# LEDs.net
KiCad netlist of a schematic drawn in Altium Designer
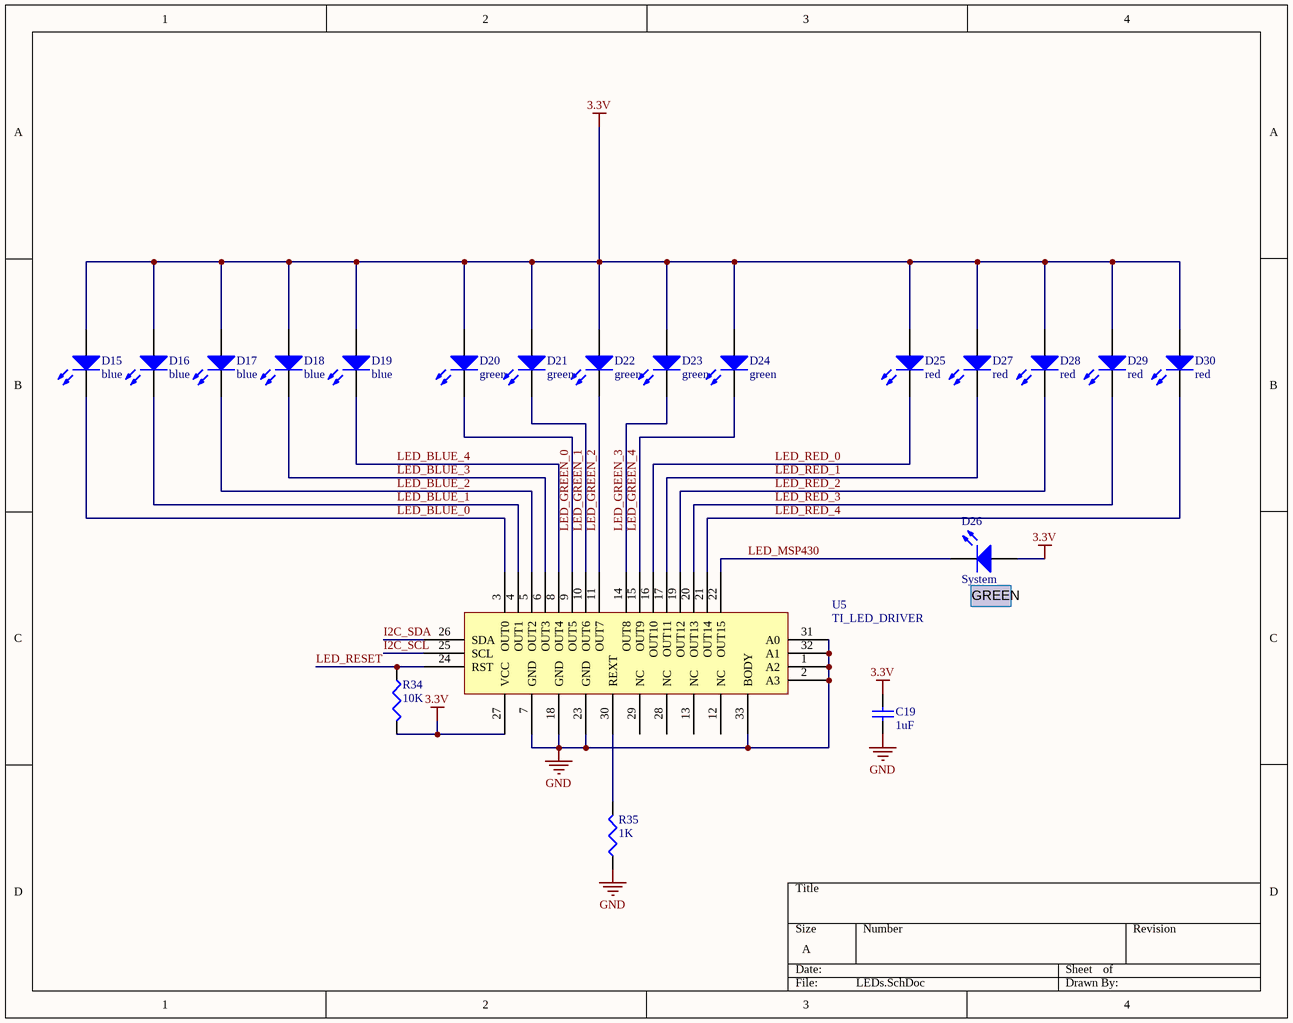
[diagram p0: LEDs.SchDoc]

(export (version "E")
  (design (tool "Eeschema 10.0.6"))
  (components
    (comp (ref "C19")
      (value "1uF")
      (footprint "CAPC1608L")
      (description "Capacitor (Semiconductor SIM Model)")
      (fields (field (name "Comment") "Cap Semi") (field (name "PUBLISHER") "Altium Limited"))
      (libsource (lib "Miscellaneous Devices") (part "Cap Semi"))
    )
    (comp (ref "D15") (value "blue") (footprint "SurfaceMount(603)") (libsource (lib "mrone") (part "LED")))
    (comp (ref "D16") (value "blue") (footprint "SurfaceMount(603)") (libsource (lib "mrone") (part "LED")))
    (comp (ref "D17") (value "blue") (footprint "SurfaceMount(603)") (libsource (lib "mrone") (part "LED")))
    (comp (ref "D18") (value "blue") (footprint "SurfaceMount(603)") (libsource (lib "mrone") (part "LED")))
    (comp (ref "D19") (value "blue") (footprint "SurfaceMount(603)") (libsource (lib "mrone") (part "LED")))
    (comp (ref "D20") (value "green") (footprint "SurfaceMount(603)") (libsource (lib "mrone") (part "LED")))
    (comp (ref "D21") (value "green") (footprint "SurfaceMount(603)") (libsource (lib "mrone") (part "LED")))
    (comp (ref "D22") (value "green") (footprint "SurfaceMount(603)") (libsource (lib "mrone") (part "LED")))
    (comp (ref "D23") (value "green") (footprint "SurfaceMount(603)") (libsource (lib "mrone") (part "LED")))
    (comp (ref "D24") (value "green") (footprint "SurfaceMount(603)") (libsource (lib "mrone") (part "LED")))
    (comp (ref "D25") (value "red") (footprint "SurfaceMount(603)") (libsource (lib "mrone") (part "LED")))
    (comp (ref "D26") (value "System") (footprint "SurfaceMount(603)") (libsource (lib "") (part "LED_1")))
    (comp (ref "D27") (value "red") (footprint "SurfaceMount(603)") (libsource (lib "mrone") (part "LED")))
    (comp (ref "D28") (value "red") (footprint "SurfaceMount(603)") (libsource (lib "mrone") (part "LED")))
    (comp (ref "D29") (value "red") (footprint "SurfaceMount(603)") (libsource (lib "mrone") (part "LED")))
    (comp (ref "D30") (value "red") (footprint "SurfaceMount(603)") (libsource (lib "mrone") (part "LED")))
    (comp (ref "R34")
      (value "10K")
      (footprint "RESC1608L")
      (description "Resistor")
      (fields (field (name "Comment") "Res3") (field (name "PUBLISHER") "Altium Limited"))
      (libsource (lib "Miscellaneous Devices") (part "Res3"))
    )
    (comp (ref "R35")
      (value "1K")
      (footprint "RESC1608L")
      (description "Resistor")
      (fields (field (name "Comment") "Res3") (field (name "PUBLISHER") "Altium Limited"))
      (libsource (lib "Miscellaneous Devices") (part "Res3"))
    )
    (comp (ref "U5")
      (value "TI_LED_DRIVER")
      (footprint "QFN32-LEDTLC59116")
      (libsource (lib "mrone") (part "TLC59116LEDDRIVER"))
    )
  )
  (nets
    (net (code "1") (name "/I2C_SCL") (class "Default")
      (node (ref "U5") (pin "25") (pinfunction "SCL_25") (pintype "passive"))
    )
    (net (code "2") (name "/I2C_SDA") (class "Default")
      (node (ref "U5") (pin "26") (pinfunction "SDA_26") (pintype "passive"))
    )
    (net (code "3") (name "/LED_BLUE_0") (class "Default")
      (node (ref "D15") (pin "2") (pinfunction "K_2") (pintype "passive"))
      (node (ref "U5") (pin "3") (pinfunction "OUT0_3") (pintype "passive"))
    )
    (net (code "4") (name "/LED_BLUE_1") (class "Default")
      (node (ref "D16") (pin "2") (pinfunction "K_2") (pintype "passive"))
      (node (ref "U5") (pin "4") (pinfunction "OUT1_4") (pintype "passive"))
    )
    (net (code "5") (name "/LED_BLUE_2") (class "Default")
      (node (ref "D17") (pin "2") (pinfunction "K_2") (pintype "passive"))
      (node (ref "U5") (pin "5") (pinfunction "OUT2_5") (pintype "passive"))
    )
    (net (code "6") (name "/LED_BLUE_3") (class "Default")
      (node (ref "D18") (pin "2") (pinfunction "K_2") (pintype "passive"))
      (node (ref "U5") (pin "6") (pinfunction "OUT3_6") (pintype "passive"))
    )
    (net (code "7") (name "/LED_BLUE_4") (class "Default")
      (node (ref "D19") (pin "2") (pinfunction "K_2") (pintype "passive"))
      (node (ref "U5") (pin "8") (pinfunction "OUT4_8") (pintype "passive"))
    )
    (net (code "8") (name "/LED_GREEN_0") (class "Default")
      (node (ref "D20") (pin "2") (pinfunction "K_2") (pintype "passive"))
      (node (ref "U5") (pin "9") (pinfunction "OUT5_9") (pintype "passive"))
    )
    (net (code "9") (name "/LED_GREEN_1") (class "Default")
      (node (ref "D21") (pin "2") (pinfunction "K_2") (pintype "passive"))
      (node (ref "U5") (pin "10") (pinfunction "OUT6_10") (pintype "passive"))
    )
    (net (code "10") (name "/LED_GREEN_2") (class "Default")
      (node (ref "D22") (pin "2") (pinfunction "K_2") (pintype "passive"))
      (node (ref "U5") (pin "11") (pinfunction "OUT7_11") (pintype "passive"))
    )
    (net (code "11") (name "/LED_GREEN_3") (class "Default")
      (node (ref "D23") (pin "2") (pinfunction "K_2") (pintype "passive"))
      (node (ref "U5") (pin "14") (pinfunction "OUT8_14") (pintype "passive"))
    )
    (net (code "12") (name "/LED_GREEN_4") (class "Default")
      (node (ref "D24") (pin "2") (pinfunction "K_2") (pintype "passive"))
      (node (ref "U5") (pin "15") (pinfunction "OUT9_15") (pintype "passive"))
    )
    (net (code "13") (name "/LED_MSP430") (class "Default")
      (node (ref "D26") (pin "2") (pinfunction "K_2") (pintype "passive"))
      (node (ref "U5") (pin "22") (pinfunction "OUT15_22") (pintype "passive"))
    )
    (net (code "14") (name "/LED_RED_0") (class "Default")
      (node (ref "D25") (pin "2") (pinfunction "K_2") (pintype "passive"))
      (node (ref "U5") (pin "16") (pinfunction "OUT10_16") (pintype "passive"))
    )
    (net (code "15") (name "/LED_RED_1") (class "Default")
      (node (ref "D27") (pin "2") (pinfunction "K_2") (pintype "passive"))
      (node (ref "U5") (pin "17") (pinfunction "OUT11_17") (pintype "passive"))
    )
    (net (code "16") (name "/LED_RED_2") (class "Default")
      (node (ref "D28") (pin "2") (pinfunction "K_2") (pintype "passive"))
      (node (ref "U5") (pin "19") (pinfunction "OUT12_19") (pintype "passive"))
    )
    (net (code "17") (name "/LED_RED_3") (class "Default")
      (node (ref "D29") (pin "2") (pinfunction "K_2") (pintype "passive"))
      (node (ref "U5") (pin "20") (pinfunction "OUT13_20") (pintype "passive"))
    )
    (net (code "18") (name "/LED_RED_4") (class "Default")
      (node (ref "D30") (pin "2") (pinfunction "K_2") (pintype "passive"))
      (node (ref "U5") (pin "21") (pinfunction "OUT14_21") (pintype "passive"))
    )
    (net (code "19") (name "/LED_RESET") (class "Default")
      (node (ref "R34") (pin "1") (pinfunction "1_1") (pintype "passive"))
      (node (ref "U5") (pin "24") (pinfunction "RST_24") (pintype "passive"))
    )
    (net (code "20") (name "3.3V") (class "Default")
      (node (ref "C19") (pin "2") (pinfunction "2_2") (pintype "passive"))
      (node (ref "D15") (pin "1") (pinfunction "A_1") (pintype "passive"))
      (node (ref "D16") (pin "1") (pinfunction "A_1") (pintype "passive"))
      (node (ref "D17") (pin "1") (pinfunction "A_1") (pintype "passive"))
      (node (ref "D18") (pin "1") (pinfunction "A_1") (pintype "passive"))
      (node (ref "D19") (pin "1") (pinfunction "A_1") (pintype "passive"))
      (node (ref "D20") (pin "1") (pinfunction "A_1") (pintype "passive"))
      (node (ref "D21") (pin "1") (pinfunction "A_1") (pintype "passive"))
      (node (ref "D22") (pin "1") (pinfunction "A_1") (pintype "passive"))
      (node (ref "D23") (pin "1") (pinfunction "A_1") (pintype "passive"))
      (node (ref "D24") (pin "1") (pinfunction "A_1") (pintype "passive"))
      (node (ref "D25") (pin "1") (pinfunction "A_1") (pintype "passive"))
      (node (ref "D26") (pin "1") (pinfunction "A_1") (pintype "passive"))
      (node (ref "D27") (pin "1") (pinfunction "A_1") (pintype "passive"))
      (node (ref "D28") (pin "1") (pinfunction "A_1") (pintype "passive"))
      (node (ref "D29") (pin "1") (pinfunction "A_1") (pintype "passive"))
      (node (ref "D30") (pin "1") (pinfunction "A_1") (pintype "passive"))
      (node (ref "R34") (pin "2") (pinfunction "2_2") (pintype "passive"))
      (node (ref "U5") (pin "27") (pinfunction "VCC_27") (pintype "passive"))
    )
    (net (code "21") (name "GND") (class "Default")
      (node (ref "C19") (pin "1") (pinfunction "1_1") (pintype "passive"))
      (node (ref "R35") (pin "1") (pinfunction "1_1") (pintype "passive"))
      (node (ref "U5") (pin "1") (pinfunction "A2_1") (pintype "passive"))
      (node (ref "U5") (pin "18") (pinfunction "GND_18") (pintype "passive"))
      (node (ref "U5") (pin "2") (pinfunction "A3_2") (pintype "passive"))
      (node (ref "U5") (pin "23") (pinfunction "GND_23") (pintype "passive"))
      (node (ref "U5") (pin "31") (pinfunction "A0_31") (pintype "passive"))
      (node (ref "U5") (pin "32") (pinfunction "A1_32") (pintype "passive"))
      (node (ref "U5") (pin "33") (pinfunction "BODY_33") (pintype "passive"))
      (node (ref "U5") (pin "7") (pinfunction "GND_7") (pintype "passive"))
    )
    (net (code "22") (name "Net-(U5-REXT)") (class "Default")
      (node (ref "R35") (pin "2") (pinfunction "2_2") (pintype "passive"))
      (node (ref "U5") (pin "30") (pinfunction "REXT_30") (pintype "passive"))
    )
    (net (code "23") (name "unconnected-(U5-NC-Pad12)") (class "Default")
      (node (ref "U5") (pin "12") (pinfunction "NC_12") (pintype "passive"))
    )
    (net (code "24") (name "unconnected-(U5-NC-Pad13)") (class "Default")
      (node (ref "U5") (pin "13") (pinfunction "NC_13") (pintype "passive"))
    )
    (net (code "25") (name "unconnected-(U5-NC-Pad28)") (class "Default")
      (node (ref "U5") (pin "28") (pinfunction "NC_28") (pintype "passive"))
    )
    (net (code "26") (name "unconnected-(U5-NC-Pad29)") (class "Default")
      (node (ref "U5") (pin "29") (pinfunction "NC_29") (pintype "passive"))
    )
  )
)
